# lm_board.net
KiCad netlist of a schematic drawn in EAGLE
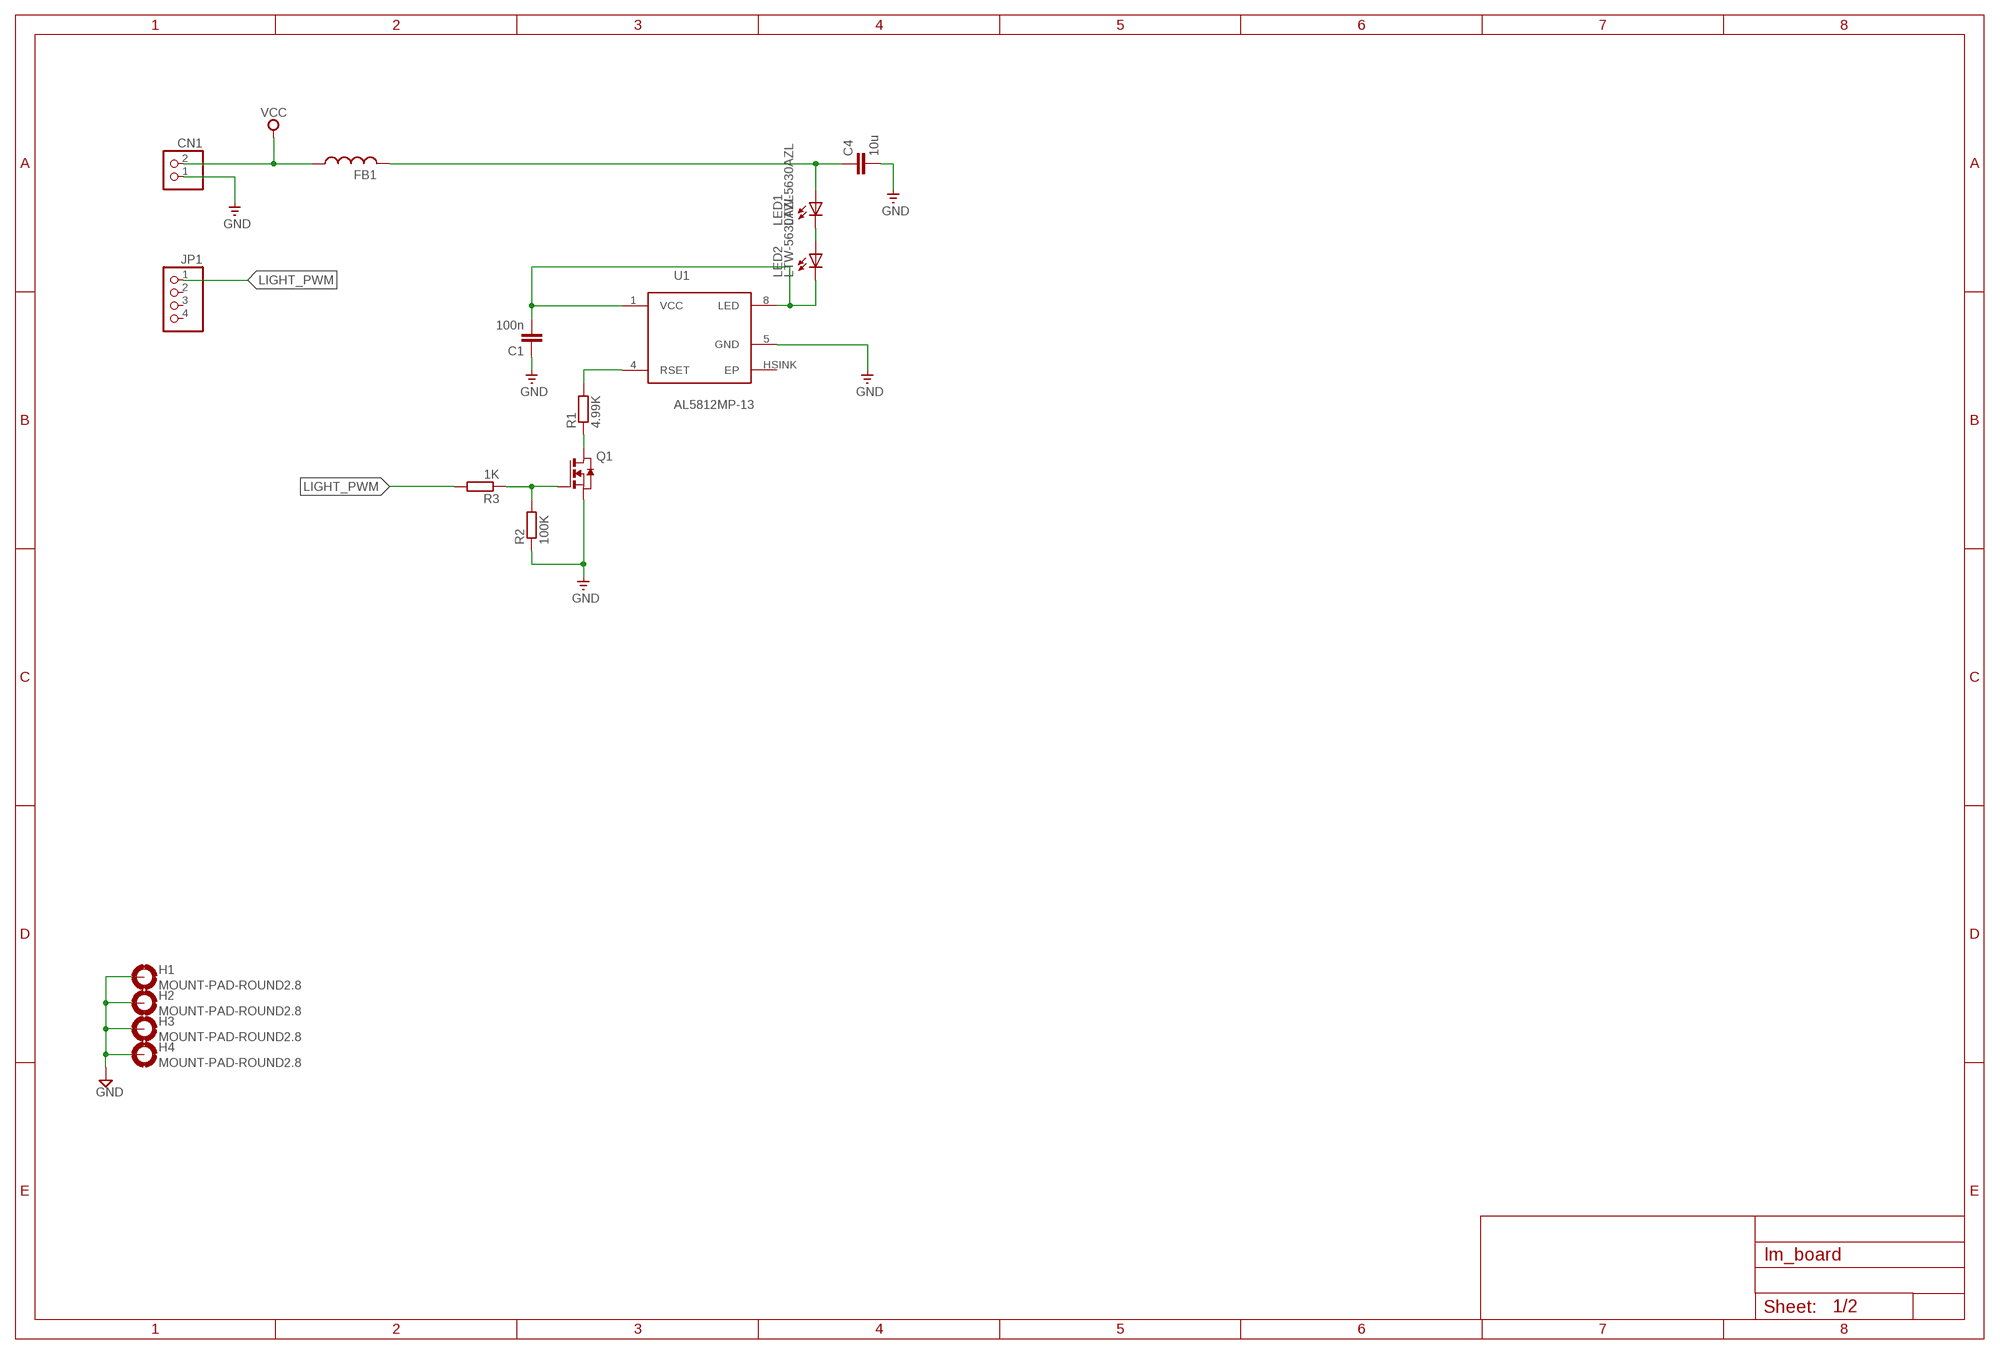
[diagram p0: schematic, sheet 1]
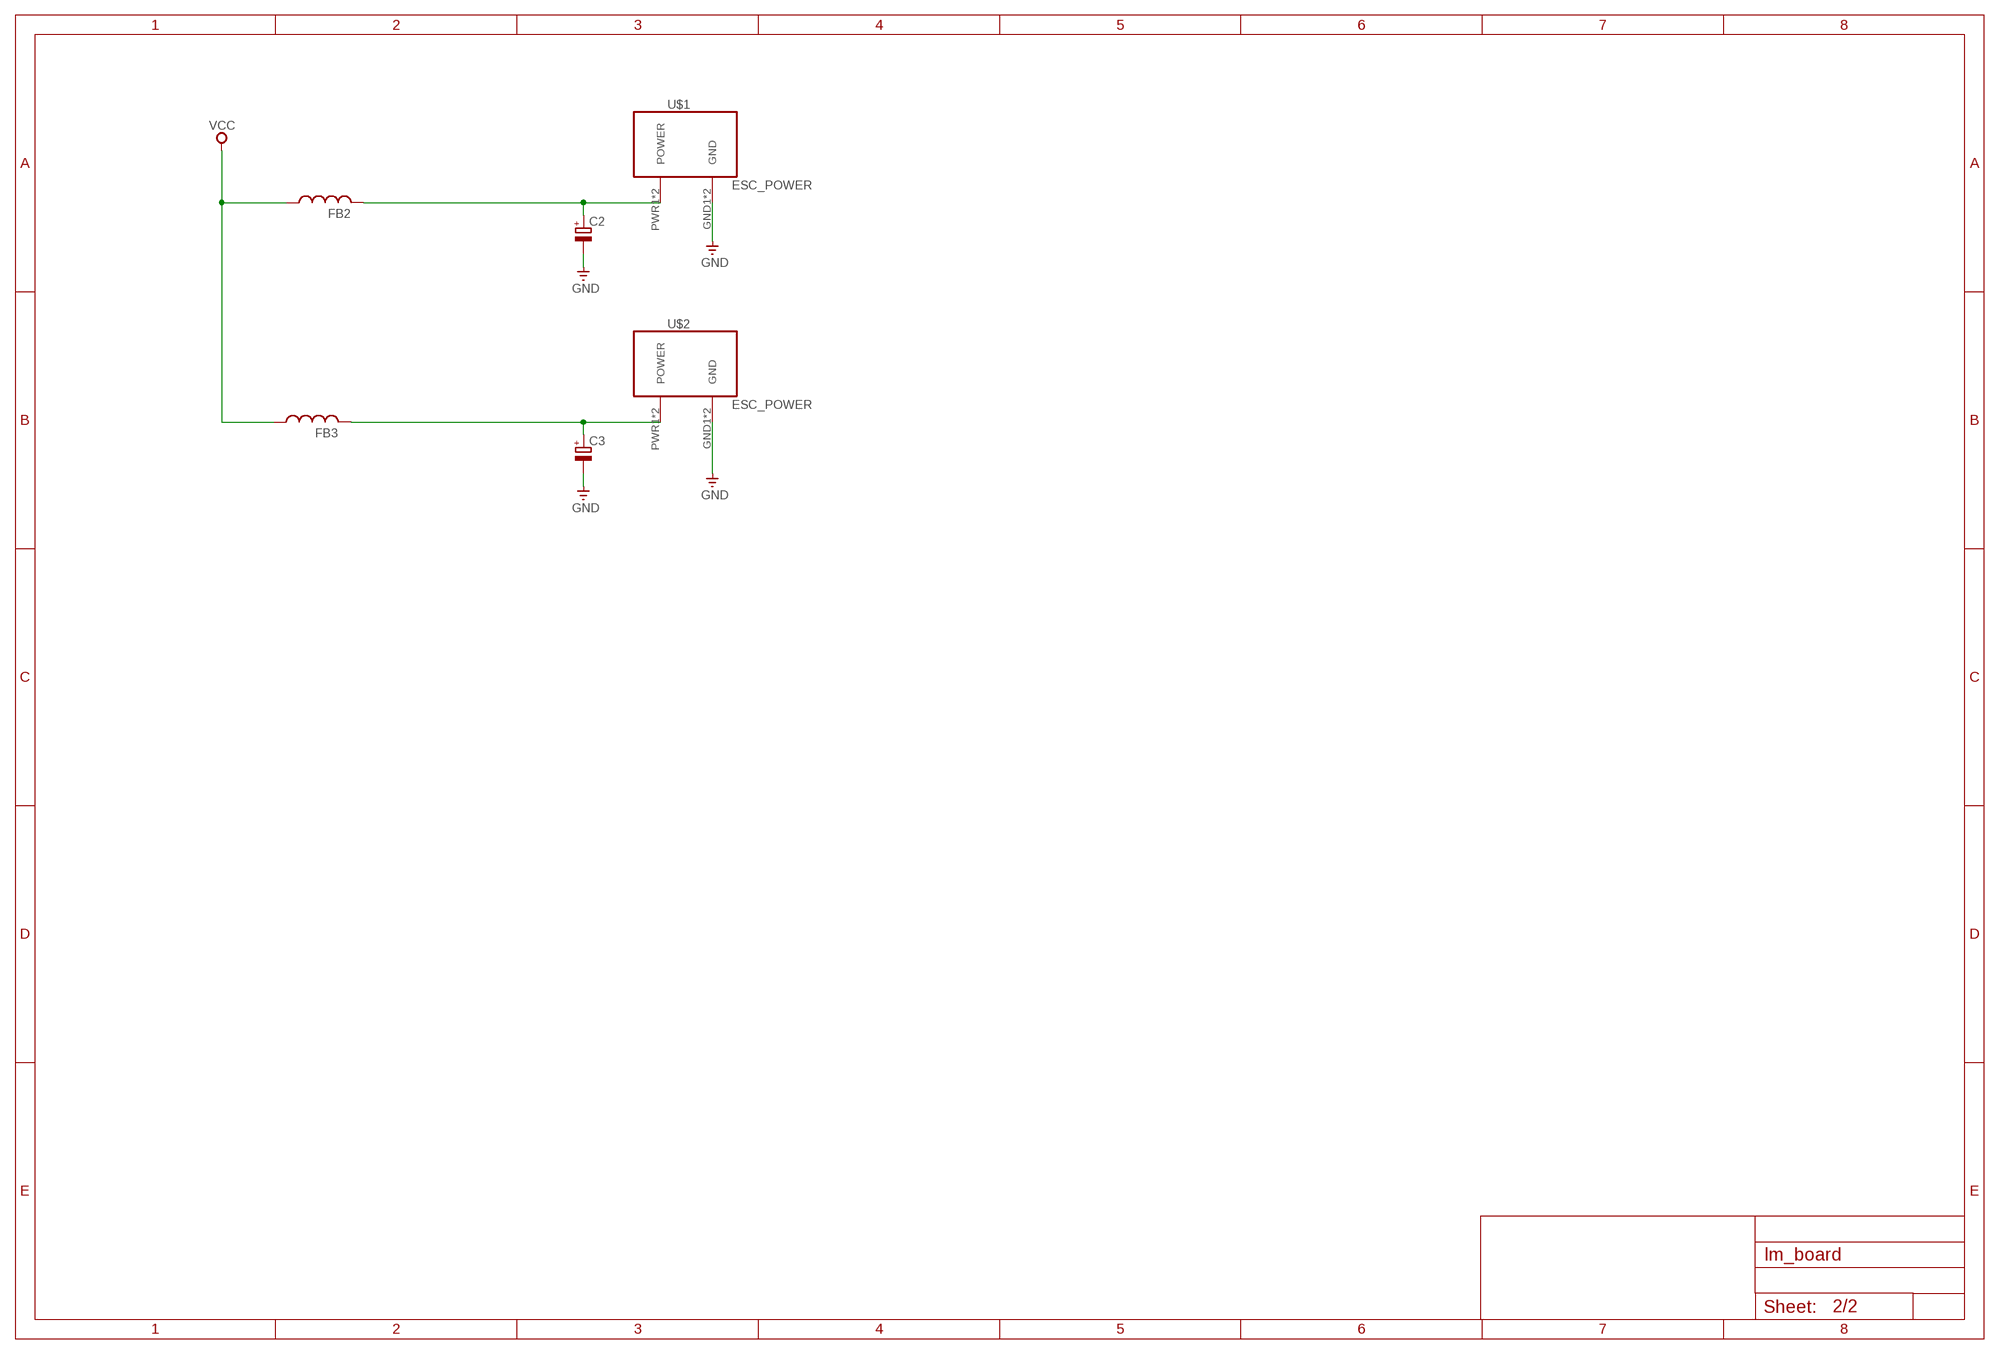
[diagram p1: schematic, sheet 2]

(export (version "E")
  (design (tool "Eeschema 10.0.6"))
  (components
    (comp (ref "C1")
      (value "100n")
      (footprint "eagle-import:C0402")
      (libsource (lib "eagle-import") (part "C-EUC0402"))
    )
    (comp (ref "C4")
      (value "10u")
      (footprint "eagle-import:C0402")
      (libsource (lib "eagle-import") (part "C-EUC0402"))
    )
    (comp (ref "CN1")
      (value "JST_2PIN-THM")
      (footprint "eagle-import:JST-PH-2-THM")
      (libsource (lib "eagle-import") (part "JST_2PIN-THM"))
    )
    (comp (ref "FB1")
      (value "FERRITESIZE_0805")
      (footprint "eagle-import:R0805")
      (libsource (lib "eagle-import") (part "FERRITESIZE_0805"))
    )
    (comp (ref "H1")
      (value "MOUNT-PAD-ROUND2.8")
      (footprint "eagle-import:2,8-PAD")
      (libsource (lib "eagle-import") (part "MOUNT-PAD-ROUND2.8"))
    )
    (comp (ref "H2")
      (value "MOUNT-PAD-ROUND2.8")
      (footprint "eagle-import:2,8-PAD")
      (libsource (lib "eagle-import") (part "MOUNT-PAD-ROUND2.8"))
    )
    (comp (ref "H3")
      (value "MOUNT-PAD-ROUND2.8")
      (footprint "eagle-import:2,8-PAD")
      (libsource (lib "eagle-import") (part "MOUNT-PAD-ROUND2.8"))
    )
    (comp (ref "H4")
      (value "MOUNT-PAD-ROUND2.8")
      (footprint "eagle-import:2,8-PAD")
      (libsource (lib "eagle-import") (part "MOUNT-PAD-ROUND2.8"))
    )
    (comp (ref "JP1")
      (value "PINHD-1X4")
      (footprint "eagle-import:1X04")
      (libsource (lib "eagle-import") (part "PINHD-1X4"))
    )
    (comp (ref "LED1")
      (value "LTW-5630AZL")
      (footprint "eagle-import:LITEON-5630")
      (libsource (lib "eagle-import") (part "LTW-5630AZL"))
    )
    (comp (ref "LED2")
      (value "LTW-5630AZL")
      (footprint "eagle-import:LITEON-5630")
      (libsource (lib "eagle-import") (part "LTW-5630AZL"))
    )
    (comp (ref "Q1")
      (value "NMOS-FETSOT23")
      (footprint "eagle-import:SOT23")
      (libsource (lib "eagle-import") (part "NMOS-FETSOT23"))
    )
    (comp (ref "R1")
      (value "4.99K")
      (footprint "eagle-import:R0402")
      (libsource (lib "eagle-import") (part "R-EU_R0402"))
    )
    (comp (ref "R2")
      (value "100K")
      (footprint "eagle-import:R0402")
      (libsource (lib "eagle-import") (part "R-EU_R0402"))
    )
    (comp (ref "R3")
      (value "1K")
      (footprint "eagle-import:R0402")
      (libsource (lib "eagle-import") (part "R-EU_R0402"))
    )
    (comp (ref "U1")
      (value "AL5812MP-13")
      (footprint "eagle-import:MSOP-8EP")
      (libsource (lib "eagle-import") (part "AL5812MP-13"))
    )
    (comp (ref "C2")
      (value "CPOL-EU153CLV-0810")
      (footprint "eagle-import:153CLV-0810")
      (libsource (lib "eagle-import") (part "CPOL-EU153CLV-0810"))
    )
    (comp (ref "C3")
      (value "CPOL-EU153CLV-0810")
      (footprint "eagle-import:153CLV-0810")
      (libsource (lib "eagle-import") (part "CPOL-EU153CLV-0810"))
    )
    (comp (ref "FB2")
      (value "FERRITESIZE_0805")
      (footprint "eagle-import:R0805")
      (libsource (lib "eagle-import") (part "FERRITESIZE_0805"))
    )
    (comp (ref "FB3")
      (value "FERRITESIZE_0805")
      (footprint "eagle-import:R0805")
      (libsource (lib "eagle-import") (part "FERRITESIZE_0805"))
    )
    (comp (ref "U$1")
      (value "ESC_POWER")
      (footprint "eagle-import:ESC_POWER")
      (libsource (lib "eagle-import") (part "ESC_POWER"))
    )
    (comp (ref "U$2")
      (value "ESC_POWER")
      (footprint "eagle-import:ESC_POWER")
      (libsource (lib "eagle-import") (part "ESC_POWER"))
    )
  )
  (nets
    (net (code "1") (name "GND") (class "Default")
      (node (ref "C1") (pin "1") (pinfunction "1_1") (pintype "passive"))
      (node (ref "C2") (pin "-") (pinfunction "-_-") (pintype "passive"))
      (node (ref "C3") (pin "-") (pinfunction "-_-") (pintype "passive"))
      (node (ref "C4") (pin "2") (pinfunction "2_2") (pintype "passive"))
      (node (ref "CN1") (pin "1") (pinfunction "2_1") (pintype "passive"))
      (node (ref "H1") (pin "B2,8") (pinfunction "MOUNT_B2,8") (pintype "passive"))
      (node (ref "H2") (pin "B2,8") (pinfunction "MOUNT_B2,8") (pintype "passive"))
      (node (ref "H3") (pin "B2,8") (pinfunction "MOUNT_B2,8") (pintype "passive"))
      (node (ref "H4") (pin "B2,8") (pinfunction "MOUNT_B2,8") (pintype "passive"))
      (node (ref "Q1") (pin "2") (pinfunction "S_2") (pintype "passive"))
      (node (ref "R2") (pin "1") (pinfunction "1_1") (pintype "passive"))
      (node (ref "U$1") (pin "GND1") (pinfunction "GND_GND1") (pintype "power_in"))
      (node (ref "U$1") (pin "GND2") (pinfunction "GND_GND2") (pintype "power_in"))
      (node (ref "U$2") (pin "GND1") (pinfunction "GND_GND1") (pintype "power_in"))
      (node (ref "U$2") (pin "GND2") (pinfunction "GND_GND2") (pintype "power_in"))
      (node (ref "U1") (pin "5") (pinfunction "GND_5") (pintype "bidirectional"))
    )
    (net (code "2") (name "LIGHT_PWM") (class "Default")
      (node (ref "JP1") (pin "1") (pinfunction "1_1") (pintype "passive"))
      (node (ref "R3") (pin "2") (pinfunction "2_2") (pintype "passive"))
    )
    (net (code "3") (name "Net-(C2-Pad+)") (class "Default")
      (node (ref "C2") (pin "+") (pinfunction "+_+") (pintype "passive"))
      (node (ref "FB2") (pin "2") (pinfunction "2_2") (pintype "passive"))
      (node (ref "U$1") (pin "PWR1") (pinfunction "POWER_PWR1") (pintype "power_in"))
      (node (ref "U$1") (pin "PWR2") (pinfunction "POWER_PWR2") (pintype "power_in"))
    )
    (net (code "4") (name "Net-(C3-Pad+)") (class "Default")
      (node (ref "C3") (pin "+") (pinfunction "+_+") (pintype "passive"))
      (node (ref "FB3") (pin "2") (pinfunction "2_2") (pintype "passive"))
      (node (ref "U$2") (pin "PWR1") (pinfunction "POWER_PWR1") (pintype "power_in"))
      (node (ref "U$2") (pin "PWR2") (pinfunction "POWER_PWR2") (pintype "power_in"))
    )
    (net (code "5") (name "Net-(C4-Pad1)") (class "Default")
      (node (ref "C4") (pin "1") (pinfunction "1_1") (pintype "passive"))
      (node (ref "FB1") (pin "2") (pinfunction "2_2") (pintype "passive"))
      (node (ref "LED1") (pin "A1") (pinfunction "A_A1") (pintype "passive"))
      (node (ref "LED1") (pin "A2") (pinfunction "A_A2") (pintype "passive"))
      (node (ref "LED1") (pin "A3") (pinfunction "A_A3") (pintype "passive"))
    )
    (net (code "6") (name "Net-(LED1-C-PadC1)") (class "Default")
      (node (ref "LED1") (pin "C1") (pinfunction "C_C1") (pintype "passive"))
      (node (ref "LED1") (pin "C2") (pinfunction "C_C2") (pintype "passive"))
      (node (ref "LED2") (pin "A1") (pinfunction "A_A1") (pintype "passive"))
      (node (ref "LED2") (pin "A2") (pinfunction "A_A2") (pintype "passive"))
      (node (ref "LED2") (pin "A3") (pinfunction "A_A3") (pintype "passive"))
    )
    (net (code "7") (name "Net-(Q1-D)") (class "Default")
      (node (ref "Q1") (pin "3") (pinfunction "D_3") (pintype "passive"))
      (node (ref "R1") (pin "1") (pinfunction "1_1") (pintype "passive"))
    )
    (net (code "8") (name "Net-(Q1-G)") (class "Default")
      (node (ref "Q1") (pin "1") (pinfunction "G_1") (pintype "passive"))
      (node (ref "R2") (pin "2") (pinfunction "2_2") (pintype "passive"))
      (node (ref "R3") (pin "1") (pinfunction "1_1") (pintype "passive"))
    )
    (net (code "9") (name "Net-(U1-LED)") (class "Default")
      (node (ref "C1") (pin "2") (pinfunction "2_2") (pintype "passive"))
      (node (ref "LED2") (pin "C1") (pinfunction "C_C1") (pintype "passive"))
      (node (ref "LED2") (pin "C2") (pinfunction "C_C2") (pintype "passive"))
      (node (ref "U1") (pin "1") (pinfunction "VCC_1") (pintype "bidirectional"))
      (node (ref "U1") (pin "8") (pinfunction "LED_8") (pintype "bidirectional"))
    )
    (net (code "10") (name "Net-(U1-RSET)") (class "Default")
      (node (ref "R1") (pin "2") (pinfunction "2_2") (pintype "passive"))
      (node (ref "U1") (pin "4") (pinfunction "RSET_4") (pintype "bidirectional"))
    )
    (net (code "11") (name "VCC") (class "Default")
      (node (ref "CN1") (pin "2") (pinfunction "1_2") (pintype "passive"))
      (node (ref "FB1") (pin "1") (pinfunction "1_1") (pintype "passive"))
      (node (ref "FB2") (pin "1") (pinfunction "1_1") (pintype "passive"))
      (node (ref "FB3") (pin "1") (pinfunction "1_1") (pintype "passive"))
    )
    (net (code "12") (name "unconnected-(JP1-Pad2)") (class "Default")
      (node (ref "JP1") (pin "2") (pinfunction "2_2") (pintype "passive"))
    )
    (net (code "13") (name "unconnected-(JP1-Pad3)") (class "Default")
      (node (ref "JP1") (pin "3") (pinfunction "3_3") (pintype "passive"))
    )
    (net (code "14") (name "unconnected-(JP1-Pad4)") (class "Default")
      (node (ref "JP1") (pin "4") (pinfunction "4_4") (pintype "passive"))
    )
    (net (code "15") (name "unconnected-(U1-EP-PadHSINK)") (class "Default")
      (node (ref "U1") (pin "HSINK") (pinfunction "EP_HSINK") (pintype "bidirectional"))
    )
  )
)
